# hand-pcb.net
KiCad netlist of a schematic drawn in EAGLE
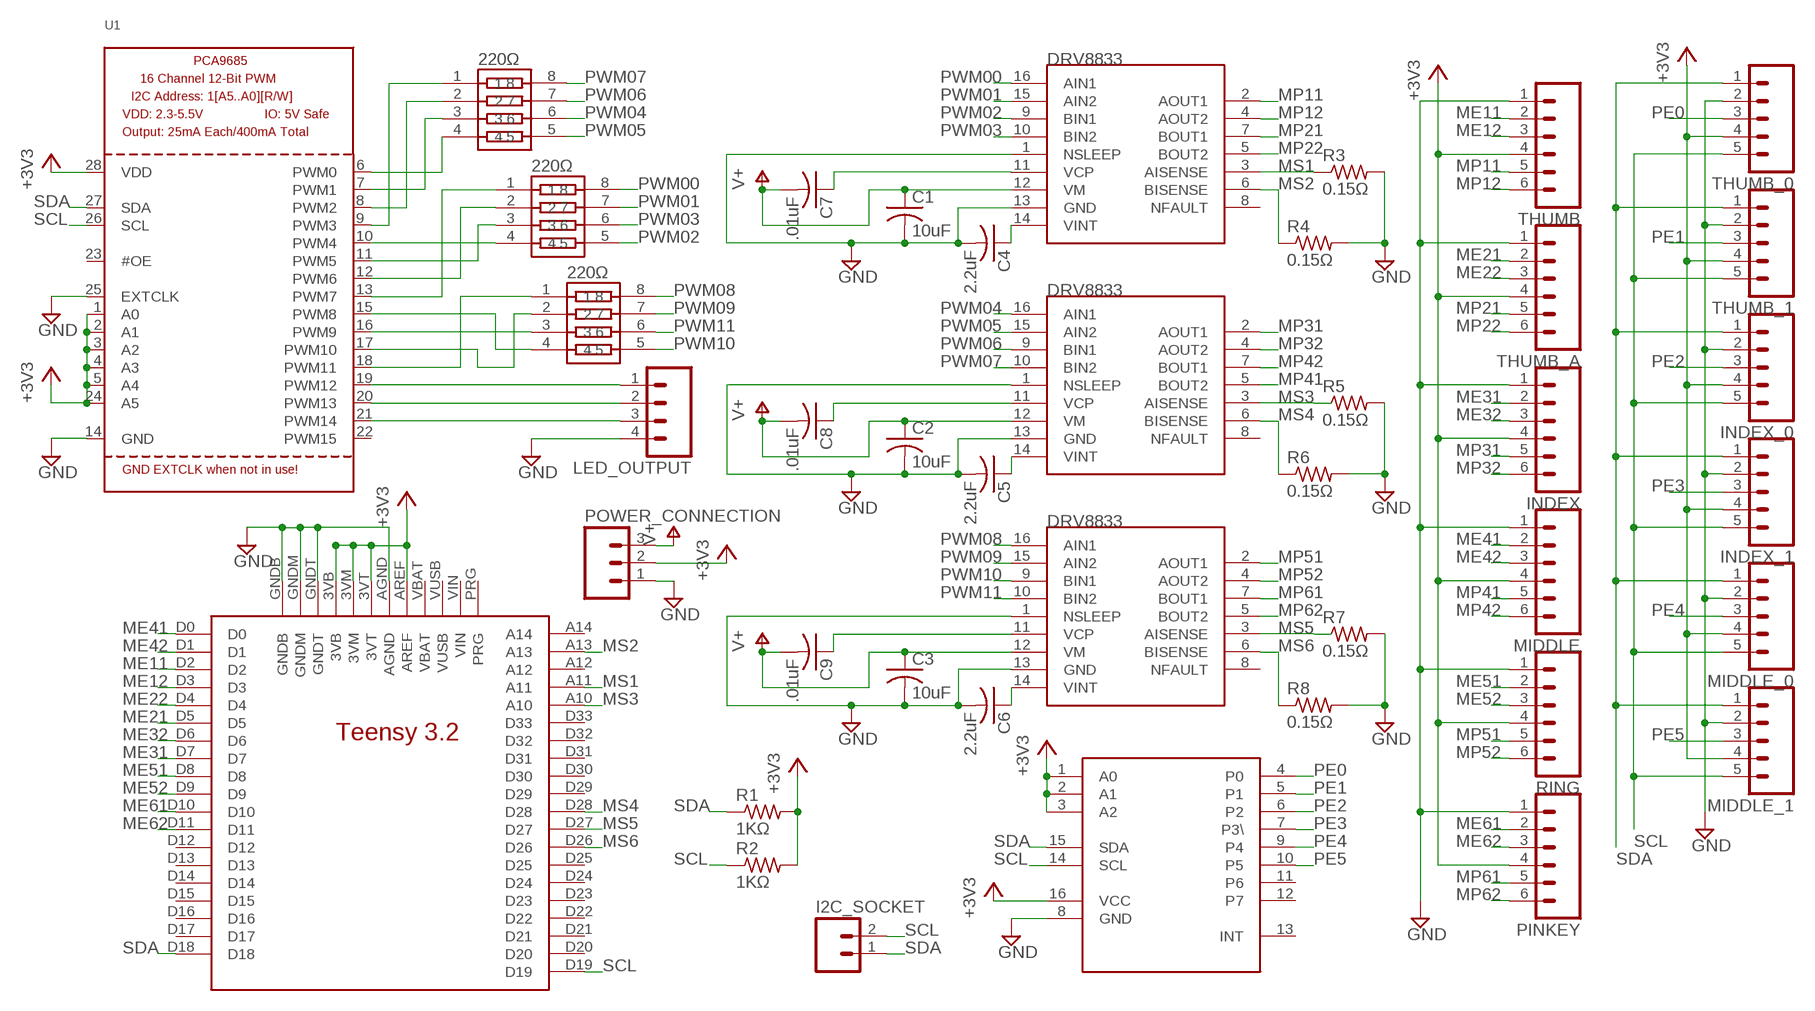
[diagram p0: schematic, sheet 1]

(export (version "E")
  (design (tool "Eeschema 10.0.6"))
  (components
    (comp (ref "220Ω")
      (value "220Ω")
      (footprint "eagle-import:RP164PJ221CS")
      (libsource (lib "eagle-import") (part "RP164PJ221CS"))
    )
    (comp (ref "C1")
      (value "10uF")
      (footprint "eagle-import:C0603")
      (libsource (lib "eagle-import") (part "C-USC0603"))
    )
    (comp (ref "C2")
      (value "10uF")
      (footprint "eagle-import:C0603")
      (libsource (lib "eagle-import") (part "C-USC0603"))
    )
    (comp (ref "C3")
      (value "10uF")
      (footprint "eagle-import:C0603")
      (libsource (lib "eagle-import") (part "C-USC0603"))
    )
    (comp (ref "C4")
      (value "2.2uF")
      (footprint "eagle-import:C0603")
      (libsource (lib "eagle-import") (part "C-USC0603"))
    )
    (comp (ref "C5")
      (value "2.2uF")
      (footprint "eagle-import:C0603")
      (libsource (lib "eagle-import") (part "C-USC0603"))
    )
    (comp (ref "C6")
      (value "2.2uF")
      (footprint "eagle-import:C0603")
      (libsource (lib "eagle-import") (part "C-USC0603"))
    )
    (comp (ref "C7")
      (value ".01uF")
      (footprint "eagle-import:C0603")
      (libsource (lib "eagle-import") (part "C-USC0603"))
    )
    (comp (ref "C8")
      (value ".01uF")
      (footprint "eagle-import:C0603")
      (libsource (lib "eagle-import") (part "C-USC0603"))
    )
    (comp (ref "C9")
      (value ".01uF")
      (footprint "eagle-import:C0603")
      (libsource (lib "eagle-import") (part "C-USC0603"))
    )
    (comp (ref "I2C_SOCKET")
      (value "M02PTH")
      (footprint "eagle-import:1X02")
      (libsource (lib "eagle-import") (part "M02PTH"))
    )
    (comp (ref "INDEX")
      (value "M06POGOPIN_HOLES_ONLY")
      (footprint "eagle-import:1X06_HOLES_ONLY")
      (libsource (lib "eagle-import") (part "M06POGOPIN_HOLES_ONLY"))
    )
    (comp (ref "INDEX_0")
      (value "M05")
      (footprint "eagle-import:1X05_HOLES_ONLY")
      (libsource (lib "eagle-import") (part "M05"))
    )
    (comp (ref "INDEX_1")
      (value "M05")
      (footprint "eagle-import:1X05_HOLES_ONLY")
      (libsource (lib "eagle-import") (part "M05"))
    )
    (comp (ref "LED_OUTPUT")
      (value "M04PTH")
      (footprint "eagle-import:1X04")
      (libsource (lib "eagle-import") (part "M04PTH"))
    )
    (comp (ref "MIDDLE")
      (value "M06POGOPIN_HOLES_ONLY")
      (footprint "eagle-import:1X06_HOLES_ONLY")
      (libsource (lib "eagle-import") (part "M06POGOPIN_HOLES_ONLY"))
    )
    (comp (ref "MIDDLE_0")
      (value "M05")
      (footprint "eagle-import:1X05_HOLES_ONLY")
      (libsource (lib "eagle-import") (part "M05"))
    )
    (comp (ref "MIDDLE_1")
      (value "M05")
      (footprint "eagle-import:1X05_HOLES_ONLY")
      (libsource (lib "eagle-import") (part "M05"))
    )
    (comp (ref "PINKEY")
      (value "M06POGOPIN_HOLES_ONLY")
      (footprint "eagle-import:1X06_HOLES_ONLY")
      (libsource (lib "eagle-import") (part "M06POGOPIN_HOLES_ONLY"))
    )
    (comp (ref "POWER_CONNECTION")
      (value "M03PTH")
      (footprint "eagle-import:1X03")
      (libsource (lib "eagle-import") (part "M03PTH"))
    )
    (comp (ref "R1")
      (value "1KΩ")
      (footprint "eagle-import:R0603")
      (libsource (lib "eagle-import") (part "R-US_R0603"))
    )
    (comp (ref "R2")
      (value "1KΩ")
      (footprint "eagle-import:R0603")
      (libsource (lib "eagle-import") (part "R-US_R0603"))
    )
    (comp (ref "R3")
      (value "0.15Ω")
      (footprint "eagle-import:M1206")
      (libsource (lib "eagle-import") (part "R-US_M1206"))
    )
    (comp (ref "R4")
      (value "0.15Ω")
      (footprint "eagle-import:M1206")
      (libsource (lib "eagle-import") (part "R-US_M1206"))
    )
    (comp (ref "R5")
      (value "0.15Ω")
      (footprint "eagle-import:M1206")
      (libsource (lib "eagle-import") (part "R-US_M1206"))
    )
    (comp (ref "R6")
      (value "0.15Ω")
      (footprint "eagle-import:M1206")
      (libsource (lib "eagle-import") (part "R-US_M1206"))
    )
    (comp (ref "R7")
      (value "0.15Ω")
      (footprint "eagle-import:M1206")
      (libsource (lib "eagle-import") (part "R-US_M1206"))
    )
    (comp (ref "R8")
      (value "0.15Ω")
      (footprint "eagle-import:M1206")
      (libsource (lib "eagle-import") (part "R-US_M1206"))
    )
    (comp (ref "RING")
      (value "M06POGOPIN_HOLES_ONLY")
      (footprint "eagle-import:1X06_HOLES_ONLY")
      (libsource (lib "eagle-import") (part "M06POGOPIN_HOLES_ONLY"))
    )
    (comp (ref "THUMB")
      (value "M06POGOPIN_HOLES_ONLY")
      (footprint "eagle-import:1X06_HOLES_ONLY")
      (libsource (lib "eagle-import") (part "M06POGOPIN_HOLES_ONLY"))
    )
    (comp (ref "THUMB_0")
      (value "M05")
      (footprint "eagle-import:1X05_HOLES_ONLY")
      (libsource (lib "eagle-import") (part "M05"))
    )
    (comp (ref "THUMB_1")
      (value "M05")
      (footprint "eagle-import:1X05_HOLES_ONLY")
      (libsource (lib "eagle-import") (part "M05"))
    )
    (comp (ref "THUMB_A")
      (value "M06POGOPIN_HOLES_ONLY")
      (footprint "eagle-import:1X06_HOLES_ONLY")
      (libsource (lib "eagle-import") (part "M06POGOPIN_HOLES_ONLY"))
    )
    (comp (ref "U$1")
      (value "DRV8833")
      (footprint "eagle-import:TSSOP16")
      (libsource (lib "eagle-import") (part "DRV8833"))
    )
    (comp (ref "U$2")
      (value "DRV8833")
      (footprint "eagle-import:TSSOP16")
      (libsource (lib "eagle-import") (part "DRV8833"))
    )
    (comp (ref "U$3")
      (value "DRV8833")
      (footprint "eagle-import:TSSOP16")
      (libsource (lib "eagle-import") (part "DRV8833"))
    )
    (comp (ref "U$4")
      (value "TEENSY32")
      (footprint "eagle-import:TEENSY32")
      (libsource (lib "eagle-import") (part "TEENSY32"))
    )
    (comp (ref "U$5")
      (value "TCA9534TSS")
      (footprint "eagle-import:TSSOP16")
      (libsource (lib "eagle-import") (part "TCA9534TSS"))
    )
    (comp (ref "U$7")
      (value "220Ω")
      (footprint "eagle-import:RP164PJ221CS")
      (libsource (lib "eagle-import") (part "RP164PJ221CS"))
    )
    (comp (ref "U$8")
      (value "220Ω")
      (footprint "eagle-import:RP164PJ221CS")
      (libsource (lib "eagle-import") (part "RP164PJ221CS"))
    )
    (comp (ref "U1")
      (value "PCA9685")
      (footprint "eagle-import:TSSOP28")
      (libsource (lib "eagle-import") (part "PCA9685"))
    )
  )
  (nets
    (net (code "1") (name "+3V3") (class "Default")
      (node (ref "INDEX") (pin "4") (pinfunction "4_4") (pintype "passive"))
      (node (ref "INDEX_0") (pin "4") (pinfunction "4_4") (pintype "passive"))
      (node (ref "INDEX_1") (pin "4") (pinfunction "4_4") (pintype "passive"))
      (node (ref "MIDDLE") (pin "4") (pinfunction "4_4") (pintype "passive"))
      (node (ref "MIDDLE_0") (pin "4") (pinfunction "4_4") (pintype "passive"))
      (node (ref "MIDDLE_1") (pin "4") (pinfunction "4_4") (pintype "passive"))
      (node (ref "PINKEY") (pin "4") (pinfunction "4_4") (pintype "passive"))
      (node (ref "POWER_CONNECTION") (pin "2") (pinfunction "2_2") (pintype "passive"))
      (node (ref "R1") (pin "2") (pinfunction "2_2") (pintype "passive"))
      (node (ref "R2") (pin "2") (pinfunction "2_2") (pintype "passive"))
      (node (ref "RING") (pin "4") (pinfunction "4_4") (pintype "passive"))
      (node (ref "THUMB") (pin "4") (pinfunction "4_4") (pintype "passive"))
      (node (ref "THUMB_0") (pin "4") (pinfunction "4_4") (pintype "passive"))
      (node (ref "THUMB_1") (pin "4") (pinfunction "4_4") (pintype "passive"))
      (node (ref "THUMB_A") (pin "4") (pinfunction "4_4") (pintype "passive"))
      (node (ref "U$4") (pin "3VB") (pinfunction "3VB_3VB") (pintype "power_in"))
      (node (ref "U$4") (pin "3VM") (pinfunction "3VM_3VM") (pintype "power_in"))
      (node (ref "U$4") (pin "3VT") (pinfunction "3VT_3VT") (pintype "power_in"))
      (node (ref "U$4") (pin "AREF") (pinfunction "AREF_AREF") (pintype "power_in"))
      (node (ref "U$5") (pin "1") (pinfunction "A0_1") (pintype "input"))
      (node (ref "U$5") (pin "16") (pinfunction "VCC_16") (pintype "power_in"))
      (node (ref "U$5") (pin "2") (pinfunction "A1_2") (pintype "input"))
      (node (ref "U$5") (pin "3") (pinfunction "A2_3") (pintype "input"))
      (node (ref "U1") (pin "1") (pinfunction "A0_1") (pintype "bidirectional"))
      (node (ref "U1") (pin "2") (pinfunction "A1_2") (pintype "bidirectional"))
      (node (ref "U1") (pin "24") (pinfunction "A5_24") (pintype "bidirectional"))
      (node (ref "U1") (pin "28") (pinfunction "VDD_28") (pintype "power_in"))
      (node (ref "U1") (pin "3") (pinfunction "A2_3") (pintype "bidirectional"))
      (node (ref "U1") (pin "4") (pinfunction "A3_4") (pintype "bidirectional"))
      (node (ref "U1") (pin "5") (pinfunction "A4_5") (pintype "bidirectional"))
    )
    (net (code "2") (name "/ME11") (class "Default")
      (node (ref "THUMB") (pin "2") (pinfunction "2_2") (pintype "passive"))
      (node (ref "U$4") (pin "D2") (pinfunction "D2_D2") (pintype "bidirectional"))
    )
    (net (code "3") (name "/ME12") (class "Default")
      (node (ref "THUMB") (pin "3") (pinfunction "3_3") (pintype "passive"))
      (node (ref "U$4") (pin "D3") (pinfunction "D3_D3") (pintype "bidirectional"))
    )
    (net (code "4") (name "/ME21") (class "Default")
      (node (ref "THUMB_A") (pin "2") (pinfunction "2_2") (pintype "passive"))
      (node (ref "U$4") (pin "D5") (pinfunction "D5_D5") (pintype "bidirectional"))
    )
    (net (code "5") (name "/ME22") (class "Default")
      (node (ref "THUMB_A") (pin "3") (pinfunction "3_3") (pintype "passive"))
      (node (ref "U$4") (pin "D4") (pinfunction "D4_D4") (pintype "bidirectional"))
    )
    (net (code "6") (name "/ME31") (class "Default")
      (node (ref "INDEX") (pin "2") (pinfunction "2_2") (pintype "passive"))
      (node (ref "U$4") (pin "D7") (pinfunction "D7_D7") (pintype "bidirectional"))
    )
    (net (code "7") (name "/ME32") (class "Default")
      (node (ref "INDEX") (pin "3") (pinfunction "3_3") (pintype "passive"))
      (node (ref "U$4") (pin "D6") (pinfunction "D6_D6") (pintype "bidirectional"))
    )
    (net (code "8") (name "/ME41") (class "Default")
      (node (ref "MIDDLE") (pin "2") (pinfunction "2_2") (pintype "passive"))
      (node (ref "U$4") (pin "D0") (pinfunction "D0_D0") (pintype "bidirectional"))
    )
    (net (code "9") (name "/ME42") (class "Default")
      (node (ref "MIDDLE") (pin "3") (pinfunction "3_3") (pintype "passive"))
      (node (ref "U$4") (pin "D1") (pinfunction "D1_D1") (pintype "bidirectional"))
    )
    (net (code "10") (name "/ME51") (class "Default")
      (node (ref "RING") (pin "2") (pinfunction "2_2") (pintype "passive"))
      (node (ref "U$4") (pin "D8") (pinfunction "D8_D8") (pintype "bidirectional"))
    )
    (net (code "11") (name "/ME52") (class "Default")
      (node (ref "RING") (pin "3") (pinfunction "3_3") (pintype "passive"))
      (node (ref "U$4") (pin "D9") (pinfunction "D9_D9") (pintype "bidirectional"))
    )
    (net (code "12") (name "/ME61") (class "Default")
      (node (ref "PINKEY") (pin "2") (pinfunction "2_2") (pintype "passive"))
      (node (ref "U$4") (pin "D10") (pinfunction "D10_D10") (pintype "bidirectional"))
    )
    (net (code "13") (name "/ME62") (class "Default")
      (node (ref "PINKEY") (pin "3") (pinfunction "3_3") (pintype "passive"))
      (node (ref "U$4") (pin "D11") (pinfunction "D11_D11") (pintype "bidirectional"))
    )
    (net (code "14") (name "/MP11") (class "Default")
      (node (ref "THUMB") (pin "5") (pinfunction "5_5") (pintype "passive"))
      (node (ref "U$1") (pin "2") (pinfunction "AOUT1_2") (pintype "output"))
    )
    (net (code "15") (name "/MP12") (class "Default")
      (node (ref "THUMB") (pin "6") (pinfunction "6_6") (pintype "passive"))
      (node (ref "U$1") (pin "4") (pinfunction "AOUT2_4") (pintype "output"))
    )
    (net (code "16") (name "/MP21") (class "Default")
      (node (ref "THUMB_A") (pin "5") (pinfunction "5_5") (pintype "passive"))
      (node (ref "U$1") (pin "7") (pinfunction "BOUT1_7") (pintype "output"))
    )
    (net (code "17") (name "/MP22") (class "Default")
      (node (ref "THUMB_A") (pin "6") (pinfunction "6_6") (pintype "passive"))
      (node (ref "U$1") (pin "5") (pinfunction "BOUT2_5") (pintype "output"))
    )
    (net (code "18") (name "/MP31") (class "Default")
      (node (ref "INDEX") (pin "5") (pinfunction "5_5") (pintype "passive"))
      (node (ref "U$2") (pin "2") (pinfunction "AOUT1_2") (pintype "output"))
    )
    (net (code "19") (name "/MP32") (class "Default")
      (node (ref "INDEX") (pin "6") (pinfunction "6_6") (pintype "passive"))
      (node (ref "U$2") (pin "4") (pinfunction "AOUT2_4") (pintype "output"))
    )
    (net (code "20") (name "/MP41") (class "Default")
      (node (ref "MIDDLE") (pin "5") (pinfunction "5_5") (pintype "passive"))
      (node (ref "U$2") (pin "5") (pinfunction "BOUT2_5") (pintype "output"))
    )
    (net (code "21") (name "/MP42") (class "Default")
      (node (ref "MIDDLE") (pin "6") (pinfunction "6_6") (pintype "passive"))
      (node (ref "U$2") (pin "7") (pinfunction "BOUT1_7") (pintype "output"))
    )
    (net (code "22") (name "/MP51") (class "Default")
      (node (ref "RING") (pin "5") (pinfunction "5_5") (pintype "passive"))
      (node (ref "U$3") (pin "2") (pinfunction "AOUT1_2") (pintype "output"))
    )
    (net (code "23") (name "/MP52") (class "Default")
      (node (ref "RING") (pin "6") (pinfunction "6_6") (pintype "passive"))
      (node (ref "U$3") (pin "4") (pinfunction "AOUT2_4") (pintype "output"))
    )
    (net (code "24") (name "/MP61") (class "Default")
      (node (ref "PINKEY") (pin "5") (pinfunction "5_5") (pintype "passive"))
      (node (ref "U$3") (pin "7") (pinfunction "BOUT1_7") (pintype "output"))
    )
    (net (code "25") (name "/MP62") (class "Default")
      (node (ref "PINKEY") (pin "6") (pinfunction "6_6") (pintype "passive"))
      (node (ref "U$3") (pin "5") (pinfunction "BOUT2_5") (pintype "output"))
    )
    (net (code "26") (name "/MS1") (class "Default")
      (node (ref "R3") (pin "1") (pinfunction "1_1") (pintype "passive"))
      (node (ref "U$1") (pin "3") (pinfunction "AISENSE_3") (pintype "output"))
      (node (ref "U$4") (pin "A11") (pinfunction "A11_A11") (pintype "input"))
    )
    (net (code "27") (name "/MS2") (class "Default")
      (node (ref "R4") (pin "1") (pinfunction "1_1") (pintype "passive"))
      (node (ref "U$1") (pin "6") (pinfunction "BISENSE_6") (pintype "output"))
      (node (ref "U$4") (pin "A13") (pinfunction "A13_A13") (pintype "input"))
    )
    (net (code "28") (name "/MS3") (class "Default")
      (node (ref "R5") (pin "1") (pinfunction "1_1") (pintype "passive"))
      (node (ref "U$2") (pin "3") (pinfunction "AISENSE_3") (pintype "output"))
      (node (ref "U$4") (pin "A10") (pinfunction "A10_A10") (pintype "input"))
    )
    (net (code "29") (name "/MS4") (class "Default")
      (node (ref "R6") (pin "1") (pinfunction "1_1") (pintype "passive"))
      (node (ref "U$2") (pin "6") (pinfunction "BISENSE_6") (pintype "output"))
      (node (ref "U$4") (pin "D28") (pinfunction "D28_D28") (pintype "bidirectional"))
    )
    (net (code "30") (name "/MS5") (class "Default")
      (node (ref "R7") (pin "1") (pinfunction "1_1") (pintype "passive"))
      (node (ref "U$3") (pin "3") (pinfunction "AISENSE_3") (pintype "output"))
      (node (ref "U$4") (pin "D27") (pinfunction "D27_D27") (pintype "bidirectional"))
    )
    (net (code "31") (name "/MS6") (class "Default")
      (node (ref "R8") (pin "1") (pinfunction "1_1") (pintype "passive"))
      (node (ref "U$3") (pin "6") (pinfunction "BISENSE_6") (pintype "output"))
      (node (ref "U$4") (pin "D26") (pinfunction "D26_D26") (pintype "bidirectional"))
    )
    (net (code "32") (name "/PE0") (class "Default")
      (node (ref "THUMB_0") (pin "3") (pinfunction "3_3") (pintype "passive"))
      (node (ref "U$5") (pin "4") (pinfunction "P0_4") (pintype "bidirectional"))
    )
    (net (code "33") (name "/PE1") (class "Default")
      (node (ref "THUMB_1") (pin "3") (pinfunction "3_3") (pintype "passive"))
      (node (ref "U$5") (pin "5") (pinfunction "P1_5") (pintype "bidirectional"))
    )
    (net (code "34") (name "/PE2") (class "Default")
      (node (ref "INDEX_0") (pin "3") (pinfunction "3_3") (pintype "passive"))
      (node (ref "U$5") (pin "6") (pinfunction "P2_6") (pintype "bidirectional"))
    )
    (net (code "35") (name "/PE3") (class "Default")
      (node (ref "INDEX_1") (pin "3") (pinfunction "3_3") (pintype "passive"))
      (node (ref "U$5") (pin "7") (pinfunction "P3\\_7") (pintype "bidirectional"))
    )
    (net (code "36") (name "/PE4") (class "Default")
      (node (ref "MIDDLE_0") (pin "3") (pinfunction "3_3") (pintype "passive"))
      (node (ref "U$5") (pin "9") (pinfunction "P4_9") (pintype "bidirectional"))
    )
    (net (code "37") (name "/PE5") (class "Default")
      (node (ref "MIDDLE_1") (pin "3") (pinfunction "3_3") (pintype "passive"))
      (node (ref "U$5") (pin "10") (pinfunction "P5_10") (pintype "bidirectional"))
    )
    (net (code "38") (name "/PRG") (class "Default")
      (node (ref "U$4") (pin "PRG") (pinfunction "PRG_PRG") (pintype "power_in"))
    )
    (net (code "39") (name "/PWM00") (class "Default")
      (node (ref "U$1") (pin "16") (pinfunction "AIN1_16") (pintype "input"))
      (node (ref "U$7") (pin "8") (pinfunction "8_8") (pintype "bidirectional"))
    )
    (net (code "40") (name "/PWM01") (class "Default")
      (node (ref "U$1") (pin "15") (pinfunction "AIN2_15") (pintype "input"))
      (node (ref "U$7") (pin "7") (pinfunction "7_7") (pintype "bidirectional"))
    )
    (net (code "41") (name "/PWM02") (class "Default")
      (node (ref "U$1") (pin "9") (pinfunction "BIN1_9") (pintype "input"))
      (node (ref "U$7") (pin "5") (pinfunction "5_5") (pintype "bidirectional"))
    )
    (net (code "42") (name "/PWM03") (class "Default")
      (node (ref "U$1") (pin "10") (pinfunction "BIN2_10") (pintype "input"))
      (node (ref "U$7") (pin "6") (pinfunction "6_6") (pintype "bidirectional"))
    )
    (net (code "43") (name "/PWM04") (class "Default")
      (node (ref "220Ω") (pin "6") (pinfunction "6_6") (pintype "bidirectional"))
      (node (ref "U$2") (pin "16") (pinfunction "AIN1_16") (pintype "input"))
    )
    (net (code "44") (name "/PWM05") (class "Default")
      (node (ref "220Ω") (pin "5") (pinfunction "5_5") (pintype "bidirectional"))
      (node (ref "U$2") (pin "15") (pinfunction "AIN2_15") (pintype "input"))
    )
    (net (code "45") (name "/PWM06") (class "Default")
      (node (ref "220Ω") (pin "7") (pinfunction "7_7") (pintype "bidirectional"))
      (node (ref "U$2") (pin "9") (pinfunction "BIN1_9") (pintype "input"))
    )
    (net (code "46") (name "/PWM07") (class "Default")
      (node (ref "220Ω") (pin "8") (pinfunction "8_8") (pintype "bidirectional"))
      (node (ref "U$2") (pin "10") (pinfunction "BIN2_10") (pintype "input"))
    )
    (net (code "47") (name "/PWM08") (class "Default")
      (node (ref "U$3") (pin "16") (pinfunction "AIN1_16") (pintype "input"))
      (node (ref "U$8") (pin "8") (pinfunction "8_8") (pintype "bidirectional"))
    )
    (net (code "48") (name "/PWM09") (class "Default")
      (node (ref "U$3") (pin "15") (pinfunction "AIN2_15") (pintype "input"))
      (node (ref "U$8") (pin "7") (pinfunction "7_7") (pintype "bidirectional"))
    )
    (net (code "49") (name "/PWM10") (class "Default")
      (node (ref "U$3") (pin "9") (pinfunction "BIN1_9") (pintype "input"))
      (node (ref "U$8") (pin "5") (pinfunction "5_5") (pintype "bidirectional"))
    )
    (net (code "50") (name "/PWM11") (class "Default")
      (node (ref "U$3") (pin "10") (pinfunction "BIN2_10") (pintype "input"))
      (node (ref "U$8") (pin "6") (pinfunction "6_6") (pintype "bidirectional"))
    )
    (net (code "51") (name "/SCL") (class "Default")
      (node (ref "I2C_SOCKET") (pin "2") (pinfunction "2_2") (pintype "passive"))
      (node (ref "INDEX_0") (pin "5") (pinfunction "5_5") (pintype "passive"))
      (node (ref "INDEX_1") (pin "5") (pinfunction "5_5") (pintype "passive"))
      (node (ref "MIDDLE_0") (pin "5") (pinfunction "5_5") (pintype "passive"))
      (node (ref "MIDDLE_1") (pin "5") (pinfunction "5_5") (pintype "passive"))
      (node (ref "R2") (pin "1") (pinfunction "1_1") (pintype "passive"))
      (node (ref "THUMB_0") (pin "5") (pinfunction "5_5") (pintype "passive"))
      (node (ref "THUMB_1") (pin "5") (pinfunction "5_5") (pintype "passive"))
      (node (ref "U$4") (pin "D19") (pinfunction "D19_D19") (pintype "bidirectional"))
      (node (ref "U$5") (pin "14") (pinfunction "SCL_14") (pintype "bidirectional"))
      (node (ref "U1") (pin "26") (pinfunction "SCL_26") (pintype "bidirectional"))
    )
    (net (code "52") (name "/SDA") (class "Default")
      (node (ref "I2C_SOCKET") (pin "1") (pinfunction "1_1") (pintype "passive"))
      (node (ref "INDEX_0") (pin "1") (pinfunction "1_1") (pintype "passive"))
      (node (ref "INDEX_1") (pin "1") (pinfunction "1_1") (pintype "passive"))
      (node (ref "MIDDLE_0") (pin "1") (pinfunction "1_1") (pintype "passive"))
      (node (ref "MIDDLE_1") (pin "1") (pinfunction "1_1") (pintype "passive"))
      (node (ref "R1") (pin "1") (pinfunction "1_1") (pintype "passive"))
      (node (ref "THUMB_0") (pin "1") (pinfunction "1_1") (pintype "passive"))
      (node (ref "THUMB_1") (pin "1") (pinfunction "1_1") (pintype "passive"))
      (node (ref "U$4") (pin "D18") (pinfunction "D18_D18") (pintype "bidirectional"))
      (node (ref "U$5") (pin "15") (pinfunction "SDA_15") (pintype "bidirectional"))
      (node (ref "U1") (pin "27") (pinfunction "SDA_27") (pintype "bidirectional"))
    )
    (net (code "53") (name "/VBAT") (class "Default")
      (node (ref "U$4") (pin "VBAT") (pinfunction "VBAT_VBAT") (pintype "power_in"))
    )
    (net (code "54") (name "/VIN") (class "Default")
      (node (ref "U$4") (pin "VIN") (pinfunction "VIN_VIN") (pintype "power_in"))
    )
    (net (code "55") (name "/VUSB") (class "Default")
      (node (ref "U$4") (pin "VUSB") (pinfunction "VUSB_VUSB") (pintype "power_in"))
    )
    (net (code "56") (name "GND") (class "Default")
      (node (ref "C1") (pin "2") (pinfunction "2_2") (pintype "passive"))
      (node (ref "C2") (pin "2") (pinfunction "2_2") (pintype "passive"))
      (node (ref "C3") (pin "2") (pinfunction "2_2") (pintype "passive"))
      (node (ref "C4") (pin "2") (pinfunction "2_2") (pintype "passive"))
      (node (ref "C5") (pin "2") (pinfunction "2_2") (pintype "passive"))
      (node (ref "C6") (pin "2") (pinfunction "2_2") (pintype "passive"))
      (node (ref "INDEX") (pin "1") (pinfunction "1_1") (pintype "passive"))
      (node (ref "INDEX_0") (pin "2") (pinfunction "2_2") (pintype "passive"))
      (node (ref "INDEX_1") (pin "2") (pinfunction "2_2") (pintype "passive"))
      (node (ref "LED_OUTPUT") (pin "4") (pinfunction "4_4") (pintype "passive"))
      (node (ref "MIDDLE") (pin "1") (pinfunction "1_1") (pintype "passive"))
      (node (ref "MIDDLE_0") (pin "2") (pinfunction "2_2") (pintype "passive"))
      (node (ref "MIDDLE_1") (pin "2") (pinfunction "2_2") (pintype "passive"))
      (node (ref "PINKEY") (pin "1") (pinfunction "1_1") (pintype "passive"))
      (node (ref "POWER_CONNECTION") (pin "1") (pinfunction "1_1") (pintype "passive"))
      (node (ref "R3") (pin "2") (pinfunction "2_2") (pintype "passive"))
      (node (ref "R4") (pin "2") (pinfunction "2_2") (pintype "passive"))
      (node (ref "R5") (pin "2") (pinfunction "2_2") (pintype "passive"))
      (node (ref "R6") (pin "2") (pinfunction "2_2") (pintype "passive"))
      (node (ref "R7") (pin "2") (pinfunction "2_2") (pintype "passive"))
      (node (ref "R8") (pin "2") (pinfunction "2_2") (pintype "passive"))
      (node (ref "RING") (pin "1") (pinfunction "1_1") (pintype "passive"))
      (node (ref "THUMB") (pin "1") (pinfunction "1_1") (pintype "passive"))
      (node (ref "THUMB_0") (pin "2") (pinfunction "2_2") (pintype "passive"))
      (node (ref "THUMB_1") (pin "2") (pinfunction "2_2") (pintype "passive"))
      (node (ref "THUMB_A") (pin "1") (pinfunction "1_1") (pintype "passive"))
      (node (ref "U$1") (pin "1") (pinfunction "NSLEEP_1") (pintype "input"))
      (node (ref "U$1") (pin "13") (pinfunction "GND_13") (pintype "power_in"))
      (node (ref "U$2") (pin "1") (pinfunction "NSLEEP_1") (pintype "input"))
      (node (ref "U$2") (pin "13") (pinfunction "GND_13") (pintype "power_in"))
      (node (ref "U$3") (pin "1") (pinfunction "NSLEEP_1") (pintype "input"))
      (node (ref "U$3") (pin "13") (pinfunction "GND_13") (pintype "power_in"))
      (node (ref "U$4") (pin "AGND") (pinfunction "AGND_AGND") (pintype "power_in"))
      (node (ref "U$4") (pin "GNDB") (pinfunction "GNDB_GNDB") (pintype "power_in"))
      (node (ref "U$4") (pin "GNDM") (pinfunction "GNDM_GNDM") (pintype "power_in"))
      (node (ref "U$4") (pin "GNDT") (pinfunction "GNDT_GNDT") (pintype "power_in"))
      (node (ref "U$5") (pin "8") (pinfunction "GND_8") (pintype "power_in"))
      (node (ref "U1") (pin "14") (pinfunction "GND_14") (pintype "power_in"))
      (node (ref "U1") (pin "25") (pinfunction "EXTCLK_25") (pintype "input"))
    )
    (net (code "57") (name "Net-(U$1-VCP)") (class "Default")
      (node (ref "C7") (pin "1") (pinfunction "1_1") (pintype "passive"))
      (node (ref "U$1") (pin "11") (pinfunction "VCP_11") (pintype "power_in"))
    )
    (net (code "58") (name "Net-(U$1-VINT)") (class "Default")
      (node (ref "C4") (pin "1") (pinfunction "1_1") (pintype "passive"))
      (node (ref "U$1") (pin "14") (pinfunction "VINT_14") (pintype "power_in"))
    )
    (net (code "59") (name "Net-(U$2-VCP)") (class "Default")
      (node (ref "C8") (pin "1") (pinfunction "1_1") (pintype "passive"))
      (node (ref "U$2") (pin "11") (pinfunction "VCP_11") (pintype "power_in"))
    )
    (net (code "60") (name "Net-(U$2-VINT)") (class "Default")
      (node (ref "C5") (pin "1") (pinfunction "1_1") (pintype "passive"))
      (node (ref "U$2") (pin "14") (pinfunction "VINT_14") (pintype "power_in"))
    )
    (net (code "61") (name "Net-(U$3-VCP)") (class "Default")
      (node (ref "C9") (pin "1") (pinfunction "1_1") (pintype "passive"))
      (node (ref "U$3") (pin "11") (pinfunction "VCP_11") (pintype "power_in"))
    )
    (net (code "62") (name "Net-(U$3-VINT)") (class "Default")
      (node (ref "C6") (pin "1") (pinfunction "1_1") (pintype "passive"))
      (node (ref "U$3") (pin "14") (pinfunction "VINT_14") (pintype "power_in"))
    )
    (net (code "63") (name "Net-(U1-PWM0)") (class "Default")
      (node (ref "220Ω") (pin "4") (pinfunction "4_4") (pintype "bidirectional"))
      (node (ref "U1") (pin "6") (pinfunction "PWM0_6") (pintype "output"))
    )
    (net (code "64") (name "Net-(U1-PWM1)") (class "Default")
      (node (ref "220Ω") (pin "3") (pinfunction "3_3") (pintype "bidirectional"))
      (node (ref "U1") (pin "7") (pinfunction "PWM1_7") (pintype "output"))
    )
    (net (code "65") (name "Net-(U1-PWM2)") (class "Default")
      (node (ref "220Ω") (pin "2") (pinfunction "2_2") (pintype "bidirectional"))
      (node (ref "U1") (pin "8") (pinfunction "PWM2_8") (pintype "output"))
    )
    (net (code "66") (name "Net-(U1-PWM3)") (class "Default")
      (node (ref "220Ω") (pin "1") (pinfunction "1_1") (pintype "bidirectional"))
      (node (ref "U1") (pin "9") (pinfunction "PWM3_9") (pintype "output"))
    )
    (net (code "67") (name "Net-(U1-PWM4)") (class "Default")
      (node (ref "U$7") (pin "4") (pinfunction "4_4") (pintype "bidirectional"))
      (node (ref "U1") (pin "10") (pinfunction "PWM4_10") (pintype "output"))
    )
    (net (code "68") (name "Net-(U1-PWM5)") (class "Default")
      (node (ref "U$7") (pin "3") (pinfunction "3_3") (pintype "bidirectional"))
      (node (ref "U1") (pin "11") (pinfunction "PWM5_11") (pintype "output"))
    )
    (net (code "69") (name "Net-(U1-PWM6)") (class "Default")
      (node (ref "U$7") (pin "2") (pinfunction "2_2") (pintype "bidirectional"))
      (node (ref "U1") (pin "12") (pinfunction "PWM6_12") (pintype "output"))
    )
    (net (code "70") (name "Net-(U1-PWM7)") (class "Default")
      (node (ref "U$7") (pin "1") (pinfunction "1_1") (pintype "bidirectional"))
      (node (ref "U1") (pin "13") (pinfunction "PWM7_13") (pintype "output"))
    )
    (net (code "71") (name "Net-(U1-PWM8)") (class "Default")
      (node (ref "U$8") (pin "4") (pinfunction "4_4") (pintype "bidirectional"))
      (node (ref "U1") (pin "15") (pinfunction "PWM8_15") (pintype "output"))
    )
    (net (code "72") (name "Net-(U1-PWM9)") (class "Default")
      (node (ref "U$8") (pin "3") (pinfunction "3_3") (pintype "bidirectional"))
      (node (ref "U1") (pin "16") (pinfunction "PWM9_16") (pintype "output"))
    )
    (net (code "73") (name "Net-(U1-PWM10)") (class "Default")
      (node (ref "U$8") (pin "2") (pinfunction "2_2") (pintype "bidirectional"))
      (node (ref "U1") (pin "17") (pinfunction "PWM10_17") (pintype "output"))
    )
    (net (code "74") (name "Net-(U1-PWM11)") (class "Default")
      (node (ref "U$8") (pin "1") (pinfunction "1_1") (pintype "bidirectional"))
      (node (ref "U1") (pin "18") (pinfunction "PWM11_18") (pintype "output"))
    )
    (net (code "75") (name "Net-(U1-PWM12)") (class "Default")
      (node (ref "LED_OUTPUT") (pin "1") (pinfunction "1_1") (pintype "passive"))
      (node (ref "U1") (pin "19") (pinfunction "PWM12_19") (pintype "output"))
    )
    (net (code "76") (name "Net-(U1-PWM13)") (class "Default")
      (node (ref "LED_OUTPUT") (pin "2") (pinfunction "2_2") (pintype "passive"))
      (node (ref "U1") (pin "20") (pinfunction "PWM13_20") (pintype "output"))
    )
    (net (code "77") (name "Net-(U1-PWM14)") (class "Default")
      (node (ref "LED_OUTPUT") (pin "3") (pinfunction "3_3") (pintype "passive"))
      (node (ref "U1") (pin "21") (pinfunction "PWM14_21") (pintype "output"))
    )
    (net (code "78") (name "V+") (class "Default")
      (node (ref "C1") (pin "1") (pinfunction "1_1") (pintype "passive"))
      (node (ref "C2") (pin "1") (pinfunction "1_1") (pintype "passive"))
      (node (ref "C3") (pin "1") (pinfunction "1_1") (pintype "passive"))
      (node (ref "C7") (pin "2") (pinfunction "2_2") (pintype "passive"))
      (node (ref "C8") (pin "2") (pinfunction "2_2") (pintype "passive"))
      (node (ref "C9") (pin "2") (pinfunction "2_2") (pintype "passive"))
      (node (ref "POWER_CONNECTION") (pin "3") (pinfunction "3_3") (pintype "passive"))
      (node (ref "U$1") (pin "12") (pinfunction "VM_12") (pintype "power_in"))
      (node (ref "U$2") (pin "12") (pinfunction "VM_12") (pintype "power_in"))
      (node (ref "U$3") (pin "12") (pinfunction "VM_12") (pintype "power_in"))
    )
    (net (code "79") (name "unconnected-(U$1-NFAULT-Pad8)") (class "Default")
      (node (ref "U$1") (pin "8") (pinfunction "NFAULT_8") (pintype "output"))
    )
    (net (code "80") (name "unconnected-(U$2-NFAULT-Pad8)") (class "Default")
      (node (ref "U$2") (pin "8") (pinfunction "NFAULT_8") (pintype "output"))
    )
    (net (code "81") (name "unconnected-(U$3-NFAULT-Pad8)") (class "Default")
      (node (ref "U$3") (pin "8") (pinfunction "NFAULT_8") (pintype "output"))
    )
    (net (code "82") (name "unconnected-(U$4-PadA12)") (class "Default")
      (node (ref "U$4") (pin "A12") (pinfunction "A12_A12") (pintype "input"))
    )
    (net (code "83") (name "unconnected-(U$4-PadA14)") (class "Default")
      (node (ref "U$4") (pin "A14") (pinfunction "A14_A14") (pintype "bidirectional"))
    )
    (net (code "84") (name "unconnected-(U$4-PadD12)") (class "Default")
      (node (ref "U$4") (pin "D12") (pinfunction "D12_D12") (pintype "bidirectional"))
    )
    (net (code "85") (name "unconnected-(U$4-PadD13)") (class "Default")
      (node (ref "U$4") (pin "D13") (pinfunction "D13_D13") (pintype "bidirectional"))
    )
    (net (code "86") (name "unconnected-(U$4-PadD14)") (class "Default")
      (node (ref "U$4") (pin "D14") (pinfunction "D14_D14") (pintype "bidirectional"))
    )
    (net (code "87") (name "unconnected-(U$4-PadD15)") (class "Default")
      (node (ref "U$4") (pin "D15") (pinfunction "D15_D15") (pintype "bidirectional"))
    )
    (net (code "88") (name "unconnected-(U$4-PadD16)") (class "Default")
      (node (ref "U$4") (pin "D16") (pinfunction "D16_D16") (pintype "bidirectional"))
    )
    (net (code "89") (name "unconnected-(U$4-PadD17)") (class "Default")
      (node (ref "U$4") (pin "D17") (pinfunction "D17_D17") (pintype "bidirectional"))
    )
    (net (code "90") (name "unconnected-(U$4-PadD20)") (class "Default")
      (node (ref "U$4") (pin "D20") (pinfunction "D20_D20") (pintype "bidirectional"))
    )
    (net (code "91") (name "unconnected-(U$4-PadD21)") (class "Default")
      (node (ref "U$4") (pin "D21") (pinfunction "D21_D21") (pintype "bidirectional"))
    )
    (net (code "92") (name "unconnected-(U$4-PadD22)") (class "Default")
      (node (ref "U$4") (pin "D22") (pinfunction "D22_D22") (pintype "bidirectional"))
    )
    (net (code "93") (name "unconnected-(U$4-PadD23)") (class "Default")
      (node (ref "U$4") (pin "D23") (pinfunction "D23_D23") (pintype "bidirectional"))
    )
    (net (code "94") (name "unconnected-(U$4-PadD24)") (class "Default")
      (node (ref "U$4") (pin "D24") (pinfunction "D24_D24") (pintype "bidirectional"))
    )
    (net (code "95") (name "unconnected-(U$4-PadD25)") (class "Default")
      (node (ref "U$4") (pin "D25") (pinfunction "D25_D25") (pintype "bidirectional"))
    )
    (net (code "96") (name "unconnected-(U$4-PadD29)") (class "Default")
      (node (ref "U$4") (pin "D29") (pinfunction "D29_D29") (pintype "bidirectional"))
    )
    (net (code "97") (name "unconnected-(U$4-PadD30)") (class "Default")
      (node (ref "U$4") (pin "D30") (pinfunction "D30_D30") (pintype "bidirectional"))
    )
    (net (code "98") (name "unconnected-(U$4-PadD31)") (class "Default")
      (node (ref "U$4") (pin "D31") (pinfunction "D31_D31") (pintype "bidirectional"))
    )
    (net (code "99") (name "unconnected-(U$4-PadD32)") (class "Default")
      (node (ref "U$4") (pin "D32") (pinfunction "D32_D32") (pintype "bidirectional"))
    )
    (net (code "100") (name "unconnected-(U$4-PadD33)") (class "Default")
      (node (ref "U$4") (pin "D33") (pinfunction "D33_D33") (pintype "bidirectional"))
    )
    (net (code "101") (name "unconnected-(U$5-INT-Pad13)") (class "Default")
      (node (ref "U$5") (pin "13") (pinfunction "INT_13") (pintype "output"))
    )
    (net (code "102") (name "unconnected-(U$5-P6-Pad11)") (class "Default")
      (node (ref "U$5") (pin "11") (pinfunction "P6_11") (pintype "bidirectional"))
    )
    (net (code "103") (name "unconnected-(U$5-P7-Pad12)") (class "Default")
      (node (ref "U$5") (pin "12") (pinfunction "P7_12") (pintype "bidirectional"))
    )
    (net (code "104") (name "unconnected-(U1-#OE-Pad23)") (class "Default")
      (node (ref "U1") (pin "23") (pinfunction "#OE_23") (pintype "input"))
    )
    (net (code "105") (name "unconnected-(U1-PWM15-Pad22)") (class "Default")
      (node (ref "U1") (pin "22") (pinfunction "PWM15_22") (pintype "output"))
    )
  )
)
